# ArduinoUnoSCHEMATIC.net
KiCad netlist of a schematic drawn in Altium Designer
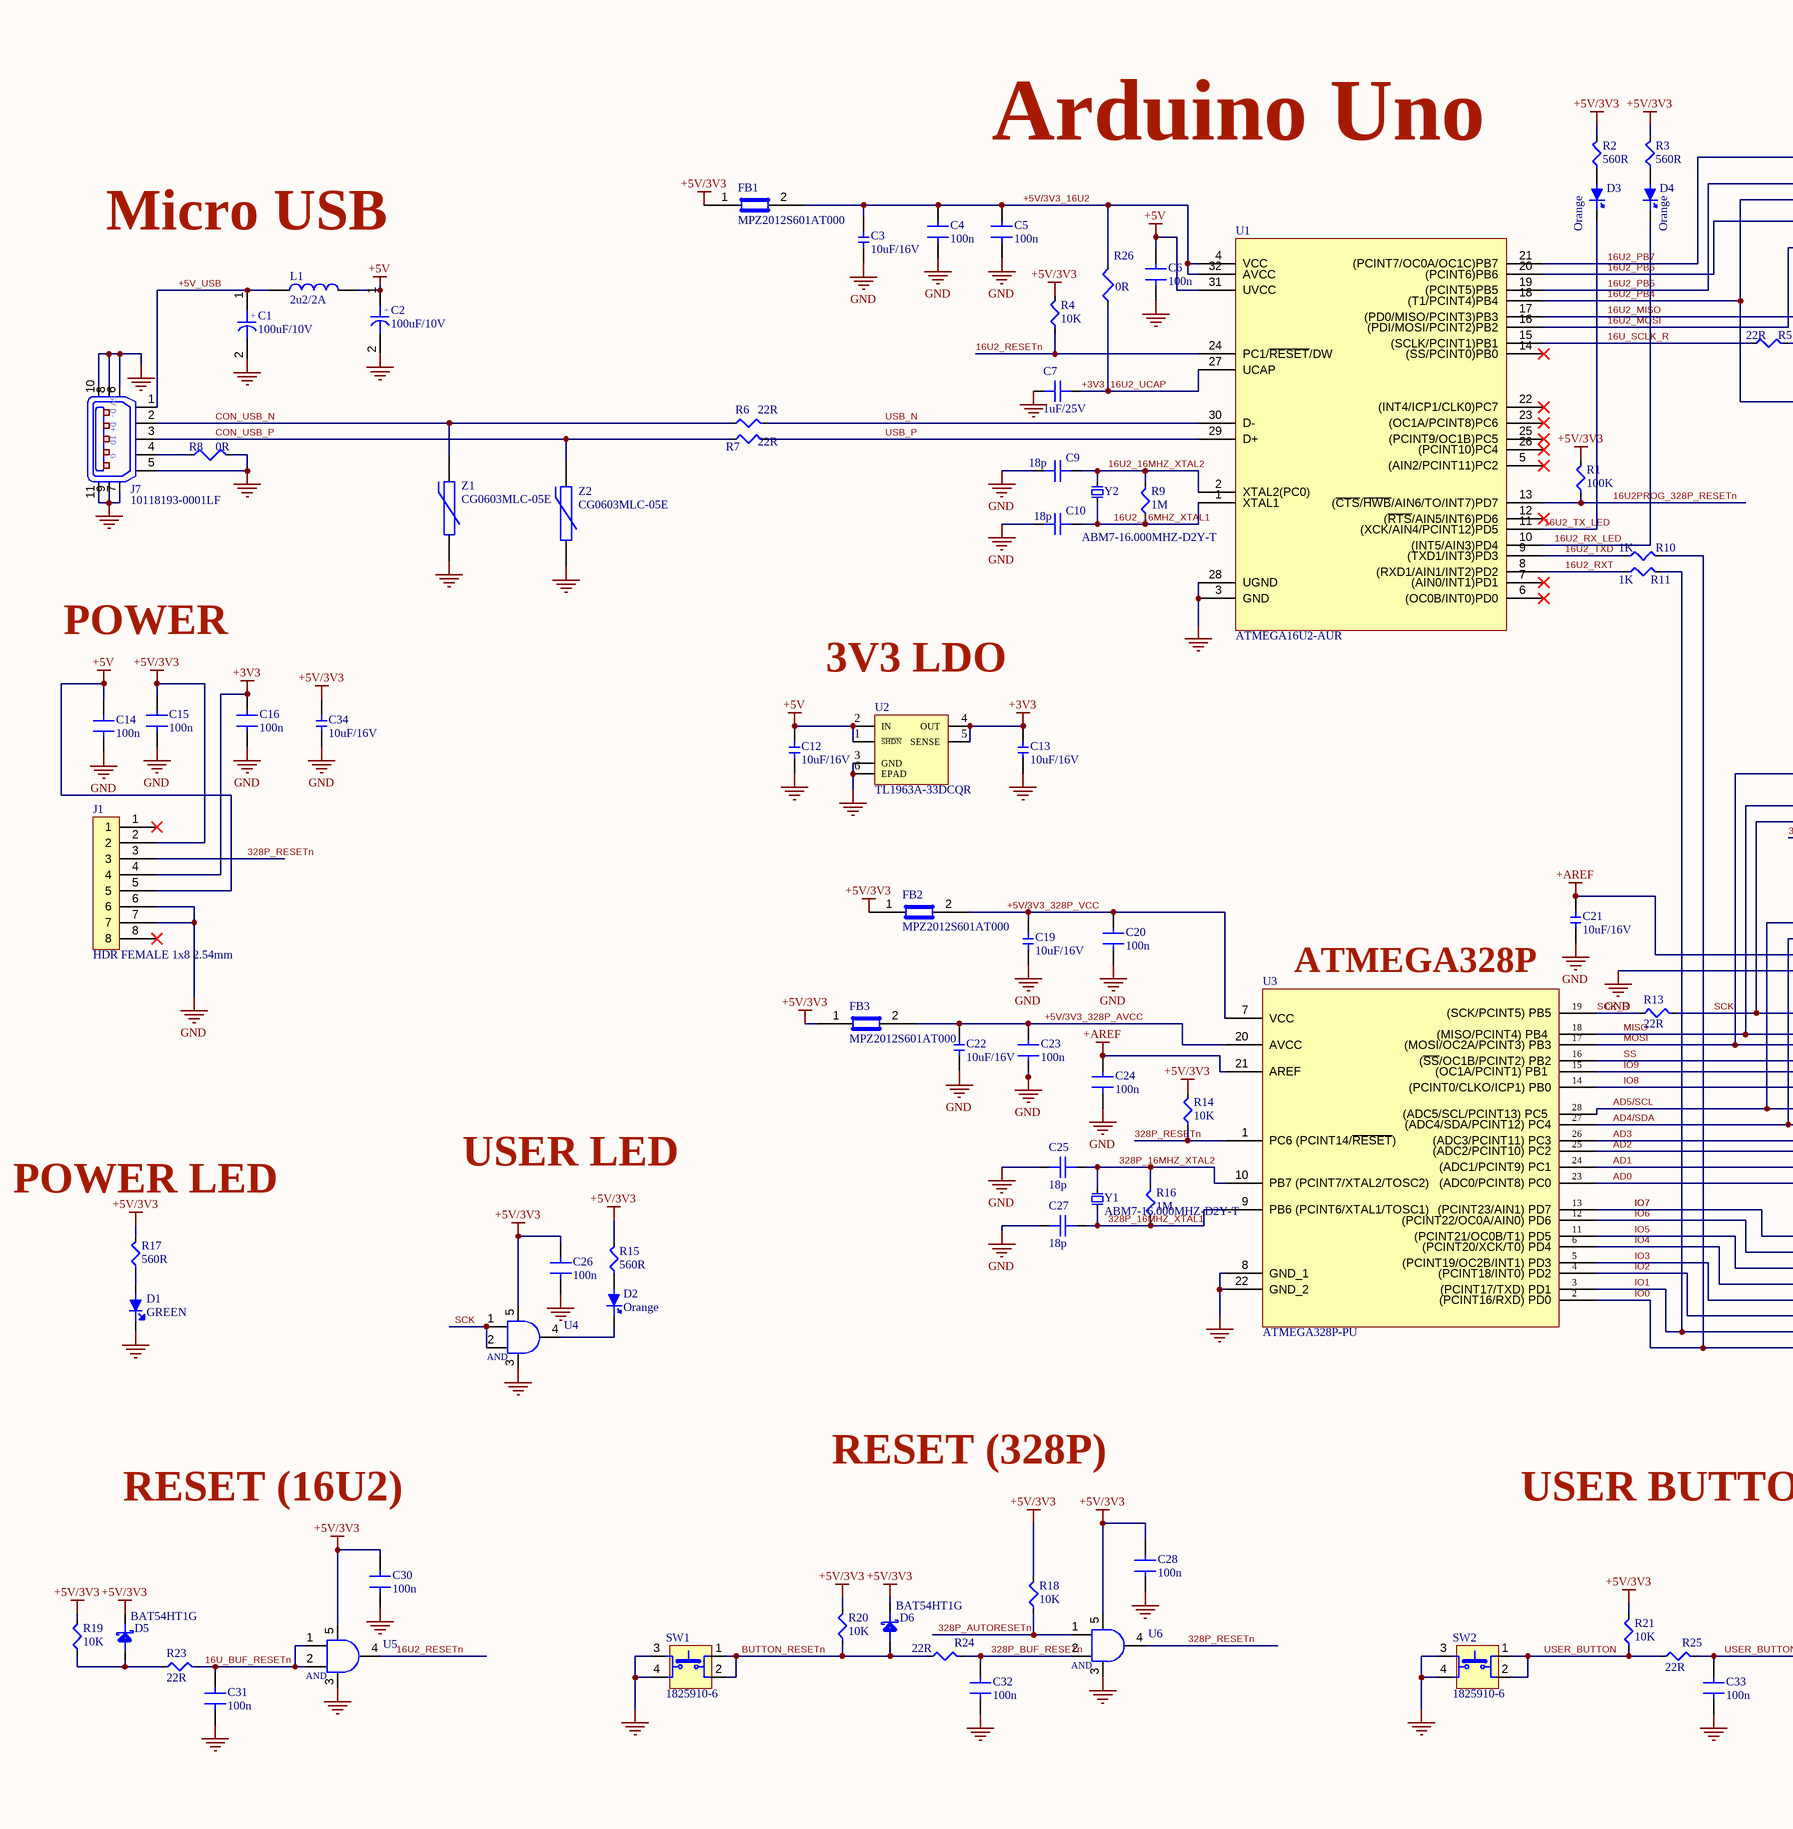
[diagram p0: ArduinoUnoSCHEMATIC.SchDoc, left]
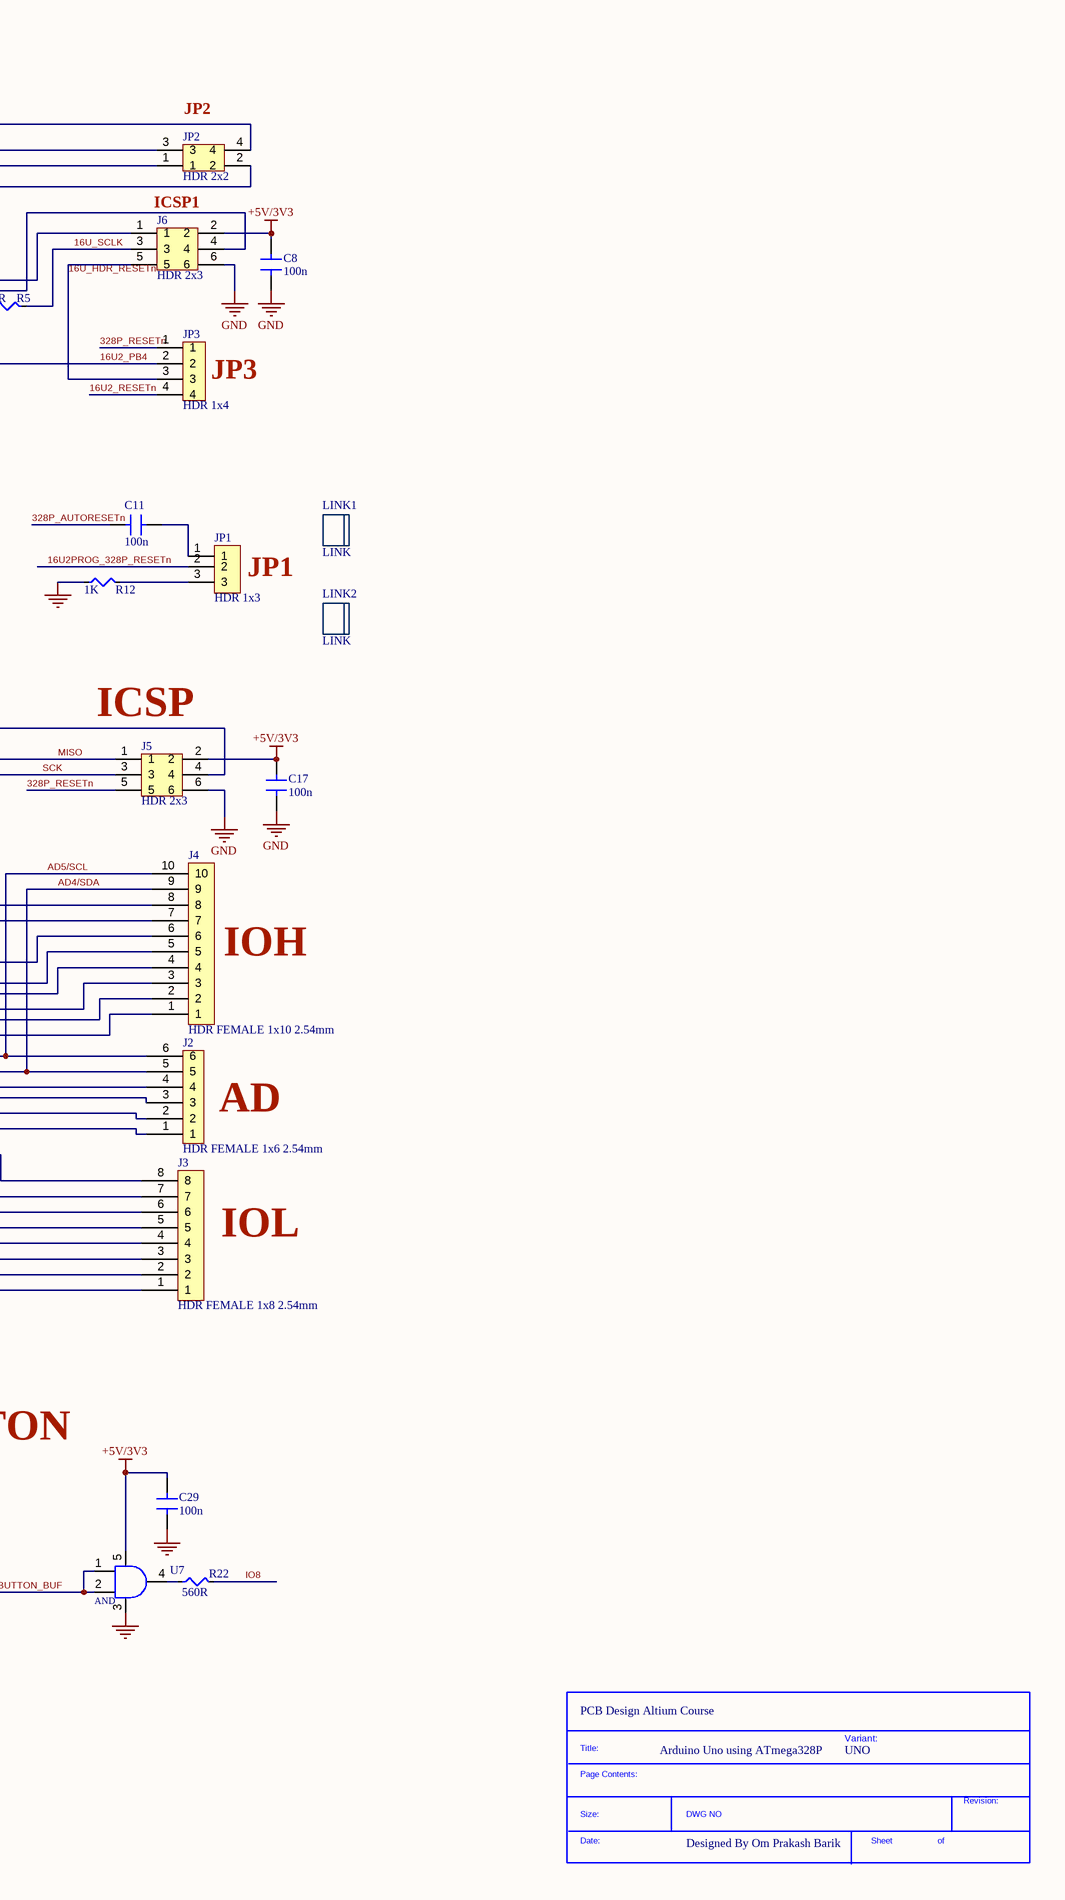
[diagram p1: ArduinoUnoSCHEMATIC.SchDoc, right]

(export (version "E")
  (design (tool "Eeschema 10.0.6"))
  (components
    (comp (ref "1") (value "~") (description "1") (libsource (lib "*") (part "SDTitleBlock")))
    (comp (ref "C1")
      (value "100uF/10V")
      (footprint "C_ALMN_CSIZE")
      (description "Cap Aluminum 100uF 10V 20% (5 X 5.4mm) SMD 50mA 1000 hr 85°C T/R")
      (fields
        (field (name "MANUFACTURER") "Panasonic")
        (field (name "MANUFACTURER PART NUMBER") "EEE-1AA101WR")
      )
      (libsource (lib "EmbedUno_V1I1") (part "100uF/10V"))
    )
    (comp (ref "C2")
      (value "100uF/10V")
      (footprint "C_ALMN_CSIZE")
      (description "Cap Aluminum 100uF 10V 20% (5 X 5.4mm) SMD 50mA 1000 hr 85°C T/R")
      (fields
        (field (name "MANUFACTURER") "Panasonic")
        (field (name "MANUFACTURER PART NUMBER") "EEE-1AA101WR")
      )
      (libsource (lib "EmbedUno_V1I1") (part "100uF/10V"))
    )
    (comp (ref "C3")
      (value "10uF/16V")
      (footprint "C0805")
      (fields
        (field (name "MANUFACTURER") "TDK")
        (field (name "MANUFACTURER PART NUMBER") "C2012X5R1C106M085AC")
        (field (name "TOLERANCE") "20%")
      )
      (libsource (lib "EmbedUno_V1I1") (part "10uF/16V"))
    )
    (comp (ref "C4")
      (value "100n")
      (footprint "C0805")
      (description "CAP CER 0.1UF 50V X7R 0805")
      (fields
        (field (name "MANUFACTURER") "TDK")
        (field (name "MANUFACTURER PART NUMBER") "C2012X7R1H104M085AA")
      )
      (libsource (lib "EmbedUno_V1I1") (part "Cap 100n"))
    )
    (comp (ref "C5")
      (value "100n")
      (footprint "C0805")
      (description "CAP CER 0.1UF 50V X7R 0805")
      (fields
        (field (name "MANUFACTURER") "TDK")
        (field (name "MANUFACTURER PART NUMBER") "C2012X7R1H104M085AA")
      )
      (libsource (lib "EmbedUno_V1I1") (part "Cap 100n"))
    )
    (comp (ref "C6")
      (value "100n")
      (footprint "C0805")
      (description "CAP CER 0.1UF 50V X7R 0805")
      (fields
        (field (name "MANUFACTURER") "TDK")
        (field (name "MANUFACTURER PART NUMBER") "C2012X7R1H104M085AA")
      )
      (libsource (lib "EmbedUno_V1I1") (part "Cap 100n"))
    )
    (comp (ref "C7")
      (value "1uF/25V")
      (footprint "C0805")
      (description "CAP CER 1UF 25V JB 0805")
      (fields
        (field (name "MANUFACTURER") "TDK")
        (field (name "MANUFACTURER PART NUMBER") "C2012JB1E105K125AA")
      )
      (libsource (lib "EmbedUno_V1I1") (part "1uF"))
    )
    (comp (ref "C8")
      (value "100n")
      (footprint "C0805")
      (description "CAP CER 0.1UF 50V X7R 0805")
      (fields
        (field (name "MANUFACTURER") "TDK")
        (field (name "MANUFACTURER PART NUMBER") "C2012X7R1H104M085AA")
      )
      (libsource (lib "EmbedUno_V1I1") (part "Cap 100n"))
    )
    (comp (ref "C9")
      (value "18p")
      (footprint "C0805")
      (description "CAP CER 18PF 50V C0G/NP0 0805")
      (fields
        (field (name "MANUFACTURER") "KEMET")
        (field (name "MANUFACTURER PART NUMBER") "C0805C180J5GACTU")
      )
      (libsource (lib "EmbedUno_V1I1") (part "C0805C180J5GACTU"))
    )
    (comp (ref "C10")
      (value "18p")
      (footprint "C0805")
      (description "CAP CER 18PF 50V C0G/NP0 0805")
      (fields
        (field (name "MANUFACTURER") "KEMET")
        (field (name "MANUFACTURER PART NUMBER") "C0805C180J5GACTU")
      )
      (libsource (lib "EmbedUno_V1I1") (part "C0805C180J5GACTU"))
    )
    (comp (ref "C11")
      (value "100n")
      (footprint "C0805")
      (description "CAP CER 0.1UF 50V X7R 0805")
      (fields
        (field (name "MANUFACTURER") "TDK")
        (field (name "MANUFACTURER PART NUMBER") "C2012X7R1H104M085AA")
      )
      (libsource (lib "EmbedUno_V1I1") (part "Cap 100n"))
    )
    (comp (ref "C12")
      (value "10uF/16V")
      (footprint "C0805")
      (fields
        (field (name "MANUFACTURER") "TDK")
        (field (name "MANUFACTURER PART NUMBER") "C2012X5R1C106M085AC")
        (field (name "TOLERANCE") "20%")
      )
      (libsource (lib "EmbedUno_V1I1") (part "10uF/16V"))
    )
    (comp (ref "C13")
      (value "10uF/16V")
      (footprint "C0805")
      (fields
        (field (name "MANUFACTURER") "TDK")
        (field (name "MANUFACTURER PART NUMBER") "C2012X5R1C106M085AC")
        (field (name "TOLERANCE") "20%")
      )
      (libsource (lib "EmbedUno_V1I1") (part "10uF/16V"))
    )
    (comp (ref "C14")
      (value "100n")
      (footprint "C0805")
      (description "CAP CER 0.1UF 50V X7R 0805")
      (fields
        (field (name "MANUFACTURER") "TDK")
        (field (name "MANUFACTURER PART NUMBER") "C2012X7R1H104M085AA")
      )
      (libsource (lib "EmbedUno_V1I1") (part "Cap 100n"))
    )
    (comp (ref "C15")
      (value "100n")
      (footprint "C0805")
      (description "CAP CER 0.1UF 50V X7R 0805")
      (fields
        (field (name "MANUFACTURER") "TDK")
        (field (name "MANUFACTURER PART NUMBER") "C2012X7R1H104M085AA")
      )
      (libsource (lib "EmbedUno_V1I1") (part "Cap 100n"))
    )
    (comp (ref "C16")
      (value "100n")
      (footprint "C0805")
      (description "CAP CER 0.1UF 50V X7R 0805")
      (fields
        (field (name "MANUFACTURER") "TDK")
        (field (name "MANUFACTURER PART NUMBER") "C2012X7R1H104M085AA")
      )
      (libsource (lib "EmbedUno_V1I1") (part "Cap 100n"))
    )
    (comp (ref "C17")
      (value "100n")
      (footprint "C0805")
      (description "CAP CER 0.1UF 50V X7R 0805")
      (fields
        (field (name "MANUFACTURER") "TDK")
        (field (name "MANUFACTURER PART NUMBER") "C2012X7R1H104M085AA")
      )
      (libsource (lib "EmbedUno_V1I1") (part "Cap 100n"))
    )
    (comp (ref "C19")
      (value "10uF/16V")
      (footprint "C0805")
      (fields
        (field (name "MANUFACTURER") "TDK")
        (field (name "MANUFACTURER PART NUMBER") "C2012X5R1C106M085AC")
        (field (name "TOLERANCE") "20%")
      )
      (libsource (lib "EmbedUno_V1I1") (part "10uF/16V"))
    )
    (comp (ref "C20")
      (value "100n")
      (footprint "C0805")
      (description "CAP CER 0.1UF 50V X7R 0805")
      (fields
        (field (name "MANUFACTURER") "TDK")
        (field (name "MANUFACTURER PART NUMBER") "C2012X7R1H104M085AA")
      )
      (libsource (lib "EmbedUno_V1I1") (part "Cap 100n"))
    )
    (comp (ref "C21")
      (value "10uF/16V")
      (footprint "C0805")
      (fields
        (field (name "MANUFACTURER") "TDK")
        (field (name "MANUFACTURER PART NUMBER") "C2012X5R1C106M085AC")
        (field (name "TOLERANCE") "20%")
      )
      (libsource (lib "EmbedUno_V1I1") (part "10uF/16V"))
    )
    (comp (ref "C22")
      (value "10uF/16V")
      (footprint "C0805")
      (fields
        (field (name "MANUFACTURER") "TDK")
        (field (name "MANUFACTURER PART NUMBER") "C2012X5R1C106M085AC")
        (field (name "TOLERANCE") "20%")
      )
      (libsource (lib "EmbedUno_V1I1") (part "10uF/16V"))
    )
    (comp (ref "C23")
      (value "100n")
      (footprint "C0805")
      (description "CAP CER 0.1UF 50V X7R 0805")
      (fields
        (field (name "MANUFACTURER") "TDK")
        (field (name "MANUFACTURER PART NUMBER") "C2012X7R1H104M085AA")
      )
      (libsource (lib "EmbedUno_V1I1") (part "Cap 100n"))
    )
    (comp (ref "C24")
      (value "100n")
      (footprint "C0805")
      (description "CAP CER 0.1UF 50V X7R 0805")
      (fields
        (field (name "MANUFACTURER") "TDK")
        (field (name "MANUFACTURER PART NUMBER") "C2012X7R1H104M085AA")
      )
      (libsource (lib "EmbedUno_V1I1") (part "Cap 100n"))
    )
    (comp (ref "C25")
      (value "18p")
      (footprint "C0805")
      (description "CAP CER 18PF 50V C0G/NP0 0805")
      (fields
        (field (name "MANUFACTURER") "KEMET")
        (field (name "MANUFACTURER PART NUMBER") "C0805C180J5GACTU")
      )
      (libsource (lib "EmbedUno_V1I1") (part "C0805C180J5GACTU"))
    )
    (comp (ref "C26")
      (value "100n")
      (footprint "C0805")
      (description "CAP CER 0.1UF 50V X7R 0805")
      (fields
        (field (name "MANUFACTURER") "TDK")
        (field (name "MANUFACTURER PART NUMBER") "C2012X7R1H104M085AA")
      )
      (libsource (lib "EmbedUno_V1I1") (part "Cap 100n"))
    )
    (comp (ref "C27")
      (value "18p")
      (footprint "C0805")
      (description "CAP CER 18PF 50V C0G/NP0 0805")
      (fields
        (field (name "MANUFACTURER") "KEMET")
        (field (name "MANUFACTURER PART NUMBER") "C0805C180J5GACTU")
      )
      (libsource (lib "EmbedUno_V1I1") (part "C0805C180J5GACTU"))
    )
    (comp (ref "C28")
      (value "100n")
      (footprint "C0805")
      (description "CAP CER 0.1UF 50V X7R 0805")
      (fields
        (field (name "MANUFACTURER") "TDK")
        (field (name "MANUFACTURER PART NUMBER") "C2012X7R1H104M085AA")
      )
      (libsource (lib "EmbedUno_V1I1") (part "Cap 100n"))
    )
    (comp (ref "C29")
      (value "100n")
      (footprint "C0805")
      (description "CAP CER 0.1UF 50V X7R 0805")
      (fields
        (field (name "MANUFACTURER") "TDK")
        (field (name "MANUFACTURER PART NUMBER") "C2012X7R1H104M085AA")
      )
      (libsource (lib "EmbedUno_V1I1") (part "Cap 100n"))
    )
    (comp (ref "C30")
      (value "100n")
      (footprint "C0805")
      (description "CAP CER 0.1UF 50V X7R 0805")
      (fields
        (field (name "MANUFACTURER") "TDK")
        (field (name "MANUFACTURER PART NUMBER") "C2012X7R1H104M085AA")
      )
      (libsource (lib "EmbedUno_V1I1") (part "Cap 100n"))
    )
    (comp (ref "C31")
      (value "100n")
      (footprint "C0805")
      (description "CAP CER 0.1UF 50V X7R 0805")
      (fields
        (field (name "MANUFACTURER") "TDK")
        (field (name "MANUFACTURER PART NUMBER") "C2012X7R1H104M085AA")
      )
      (libsource (lib "EmbedUno_V1I1") (part "Cap 100n"))
    )
    (comp (ref "C32")
      (value "100n")
      (footprint "C0805")
      (description "CAP CER 0.1UF 50V X7R 0805")
      (fields
        (field (name "MANUFACTURER") "TDK")
        (field (name "MANUFACTURER PART NUMBER") "C2012X7R1H104M085AA")
      )
      (libsource (lib "EmbedUno_V1I1") (part "Cap 100n"))
    )
    (comp (ref "C33")
      (value "100n")
      (footprint "C0805")
      (description "CAP CER 0.1UF 50V X7R 0805")
      (fields
        (field (name "MANUFACTURER") "TDK")
        (field (name "MANUFACTURER PART NUMBER") "C2012X7R1H104M085AA")
      )
      (libsource (lib "EmbedUno_V1I1") (part "Cap 100n"))
    )
    (comp (ref "C34")
      (value "10uF/16V")
      (footprint "C0805")
      (fields
        (field (name "MANUFACTURER") "TDK")
        (field (name "MANUFACTURER PART NUMBER") "C2012X5R1C106M085AC")
        (field (name "TOLERANCE") "20%")
      )
      (libsource (lib "EmbedUno_V1I1") (part "10uF/16V"))
    )
    (comp (ref "D1")
      (value "GREEN")
      (footprint "LED_0603")
      (description "LED Uni-Color Green 572nm 2-Pin Chip 0603(1608Metric) T/R")
      (fields
        (field (name "MANUFACTURER") "Osram Opto")
        (field (name "MANUFACTURER PART NUMBER") "LGL29K-G2J1-24-Z")
      )
      (libsource (lib "EmbedUno_V1I1") (part "GREEN"))
    )
    (comp (ref "D2")
      (value "Orange")
      (footprint "LED_0603")
      (description "OSRAM - LO L29K-H2K1-24-Z - SMARTLED 0603 ORANGE")
      (fields
        (field (name "MANUFACTURER") "Osram Opto")
        (field (name "MANUFACTURER PART NUMBER") "LOL29K-H2K1-24-Z")
      )
      (libsource (lib "EmbedUno_V1I1") (part "Orange LED"))
    )
    (comp (ref "D3")
      (value "Orange")
      (footprint "LED_0603")
      (description "OSRAM - LO L29K-H2K1-24-Z - SMARTLED 0603 ORANGE")
      (fields
        (field (name "MANUFACTURER") "Osram Opto")
        (field (name "MANUFACTURER PART NUMBER") "LOL29K-H2K1-24-Z")
      )
      (libsource (lib "EmbedUno_V1I1") (part "Orange LED"))
    )
    (comp (ref "D4")
      (value "Orange")
      (footprint "LED_0603")
      (description "OSRAM - LO L29K-H2K1-24-Z - SMARTLED 0603 ORANGE")
      (fields
        (field (name "MANUFACTURER") "Osram Opto")
        (field (name "MANUFACTURER PART NUMBER") "LOL29K-H2K1-24-Z")
      )
      (libsource (lib "EmbedUno_V1I1") (part "Orange LED"))
    )
    (comp (ref "D5")
      (value "BAT54HT1G")
      (footprint "SOD323")
      (description "Small Signal Schottky Diode, Single, 30 V, 200 mA, 800 mV, 600 mA, 150 C ;RoHS Compliant: Yes")
      (fields (field (name "MANUFACTURER") "ON Semiconductor / Fairchild"))
      (libsource (lib "EmbedUno_V1I1") (part "BAT54HT1G"))
    )
    (comp (ref "D6")
      (value "BAT54HT1G")
      (footprint "SOD323")
      (description "Small Signal Schottky Diode, Single, 30 V, 200 mA, 800 mV, 600 mA, 150 C ;RoHS Compliant: Yes")
      (fields (field (name "MANUFACTURER") "ON Semiconductor / Fairchild"))
      (libsource (lib "EmbedUno_V1I1") (part "BAT54HT1G"))
    )
    (comp (ref "FB1")
      (value "MPZ2012S601AT000")
      (footprint "C0805")
      (description "FERRITE BEAD 600 OHM 0805 1LN")
      (fields (field (name "MANUFACTURER") "TDK"))
      (libsource (lib "EmbedUno_V1I1") (part "MPZ2012S601AT000"))
    )
    (comp (ref "FB2")
      (value "MPZ2012S601AT000")
      (footprint "C0805")
      (description "FERRITE BEAD 600 OHM 0805 1LN")
      (fields (field (name "MANUFACTURER") "TDK"))
      (libsource (lib "EmbedUno_V1I1") (part "MPZ2012S601AT000"))
    )
    (comp (ref "FB3")
      (value "MPZ2012S601AT000")
      (footprint "C0805")
      (description "FERRITE BEAD 600 OHM 0805 1LN")
      (fields (field (name "MANUFACTURER") "TDK"))
      (libsource (lib "EmbedUno_V1I1") (part "MPZ2012S601AT000"))
    )
    (comp (ref "J1")
      (value "HDR FEMALE 1x8 2.54mm")
      (footprint "HDR_Female_1x8_2.54mm")
      (description "2.54mm (0.1\") Pitch SIL Vertical PC Tail Socket Assembly, selective gold + tin, 8 contacts")
      (fields (field (name "MANUFACTURER") "Harwin") (field (name "MANUFACTURER PART NUMBER") "M20-7820842"))
      (libsource (lib "EmbedUno_V1I1") (part "M20-7820842"))
    )
    (comp (ref "J2")
      (value "HDR FEMALE 1x6 2.54mm")
      (footprint "HDR_Female_1x6_2.54mm")
      (fields (field (name "MANUFACTURER") "Harwin") (field (name "MANUFACTURER PART NUMBER") "M20-7820646"))
      (libsource (lib "EmbedUno_V1I1") (part "M20-7820646"))
    )
    (comp (ref "J3")
      (value "HDR FEMALE 1x8 2.54mm")
      (footprint "HDR_Female_1x8_2.54mm")
      (description "2.54mm (0.1\") Pitch SIL Vertical PC Tail Socket Assembly, selective gold + tin, 8 contacts")
      (fields (field (name "MANUFACTURER") "Harwin") (field (name "MANUFACTURER PART NUMBER") "M20-7820842"))
      (libsource (lib "") (part "M20-7820842_1"))
    )
    (comp (ref "J4")
      (value "HDR FEMALE 1x10 2.54mm")
      (footprint "HDR_Female_1x10_2.54mm")
      (fields (field (name "MANUFACTURER") "Harwin") (field (name "MANUFACTURER PART NUMBER") "M20-7821046"))
      (libsource (lib "EmbedUno_V1I1") (part "M20-7821046"))
    )
    (comp (ref "J5")
      (value "HDR 2x3")
      (footprint "HDR 2x3")
      (description "CONN HEADER 6POS .100 STR 30AU")
      (fields
        (field (name "MANUFACTURER") "Amphenol FCI")
        (field (name "MANUFACTURER PART NUMBER") "67997-106HLF")
      )
      (libsource (lib "EmbedUno_V1I1") (part "HDR 2x3"))
    )
    (comp (ref "J6")
      (value "HDR 2x3")
      (footprint "HDR 2x3")
      (description "CONN HEADER 6POS .100 STR 30AU")
      (fields
        (field (name "MANUFACTURER") "Amphenol FCI")
        (field (name "MANUFACTURER PART NUMBER") "67997-106HLF")
      )
      (libsource (lib "EmbedUno_V1I1") (part "HDR 2x3"))
    )
    (comp (ref "J7")
      (value "10118193-0001LF")
      (footprint "10118193-0001LF")
      (description "CONN USB MICRO B RECPT SMT R/A")
      (fields (field (name "MANUFACTURER") "Amphenol FCI"))
      (libsource (lib "EmbedUno_V1I1") (part "USB_CON"))
    )
    (comp (ref "JP1")
      (value "HDR 1x3")
      (footprint "HDR_Male_1x3_2.54mm")
      (fields
        (field (name "MANUFACTURER") "Amphenol FCI")
        (field (name "MANUFACTURER PART NUMBER") "68000-103HLF")
      )
      (libsource (lib "EmbedUno_V1I1") (part "68000-103HLF"))
    )
    (comp (ref "JP2")
      (value "HDR 2x2")
      (footprint "HDR 2x2_2.54mm")
      (description "CONN HEADER VERT 4POS 2.54MM")
      (fields
        (field (name "MANUFACTURER") "Amphenol FCI")
        (field (name "MANUFACTURER PART NUMBER") "68602-204HLF")
      )
      (libsource (lib "EmbedUno_V1I1") (part "HDR_2x2"))
    )
    (comp (ref "JP3")
      (value "HDR 1x4")
      (footprint "HDR_1x4_2.54mm")
      (description "CONN HEADER VERT 4POS 2.54MM")
      (fields
        (field (name "MANUFACTURER") "Amphenol FCI")
        (field (name "MANUFACTURER PART NUMBER") "68001-204HLF")
      )
      (libsource (lib "EmbedUno_V1I1") (part "HDR 1x4"))
    )
    (comp (ref "L1")
      (value "2u2/2A")
      (footprint "CL210_IND")
      (description "FIXED IND 2.2UH 2A 80 MOHM SMD")
      (fields
        (field (name "MANUFACTURER") "KEMET")
        (field (name "MANUFACTURER PART NUMBER") "L1210R2R2MDWIT")
      )
      (libsource (lib "EmbedUno_V1I1") (part "2u2/2A"))
    )
    (comp (ref "LINK1")
      (value "LINK")
      (description "CONN JUMPER SHORTING .100\" GOLD")
      (fields
        (field (name "MANUFACTURER") "Sullins")
        (field (name "MANUFACTURER PART NUMBER") "QPC02SXGN-RC")
      )
      (libsource (lib "EmbedUno_V1I1") (part "LINK"))
    )
    (comp (ref "LINK2")
      (value "LINK")
      (description "CONN JUMPER SHORTING .100\" GOLD")
      (fields
        (field (name "MANUFACTURER") "Sullins")
        (field (name "MANUFACTURER PART NUMBER") "QPC02SXGN-RC")
      )
      (libsource (lib "EmbedUno_V1I1") (part "LINK"))
    )
    (comp (ref "R1")
      (value "100K")
      (footprint "R0805")
      (description "RES SMD 100K OHM 0.1% 1/8W 0805")
      (fields
        (field (name "MANUFACTURER") "Yageo")
        (field (name "MANUFACTURER PART NUMBER") "RT0805BRD07100KL")
      )
      (libsource (lib "EmbedUno_V1I1") (part "100K"))
    )
    (comp (ref "R2")
      (value "560R")
      (footprint "R0805")
      (description "RES SMD 560 OHM 1% 1/8W 0805")
      (fields
        (field (name "MANUFACTURER") "Yageo")
        (field (name "MANUFACTURER PART NUMBER") "RT0805FRE07560RL")
      )
      (libsource (lib "EmbedUno_V1I1") (part "560R"))
    )
    (comp (ref "R3")
      (value "560R")
      (footprint "R0805")
      (description "RES SMD 560 OHM 1% 1/8W 0805")
      (fields
        (field (name "MANUFACTURER") "Yageo")
        (field (name "MANUFACTURER PART NUMBER") "RT0805FRE07560RL")
      )
      (libsource (lib "EmbedUno_V1I1") (part "560R"))
    )
    (comp (ref "R4")
      (value "10K")
      (footprint "R0805")
      (description "Res SMD 10K Ohm 1% 1/8W 0805")
      (fields
        (field (name "MANUFACTURER") "Yageo")
        (field (name "MANUFACTURER PART NUMBER") "AF0805FR-0710KL")
      )
      (libsource (lib "EmbedUno_V1I1") (part "AF0805FR-0710KL"))
    )
    (comp (ref "R5")
      (value "22R")
      (footprint "R0805")
      (description "RES SMD 22 OHM 1% 1/8W 0805")
      (fields
        (field (name "MANUFACTURER") "Yageo")
        (field (name "MANUFACTURER PART NUMBER") "RC0805FR-0722RL")
      )
      (libsource (lib "EmbedUno_V1I1") (part "RC0805FR-0722RL"))
    )
    (comp (ref "R6")
      (value "22R")
      (footprint "R0805")
      (description "RES SMD 22 OHM 1% 1/8W 0805")
      (fields
        (field (name "MANUFACTURER") "Yageo")
        (field (name "MANUFACTURER PART NUMBER") "RC0805FR-0722RL")
      )
      (libsource (lib "EmbedUno_V1I1") (part "RC0805FR-0722RL"))
    )
    (comp (ref "R7")
      (value "22R")
      (footprint "R0805")
      (description "RES SMD 22 OHM 1% 1/8W 0805")
      (fields
        (field (name "MANUFACTURER") "Yageo")
        (field (name "MANUFACTURER PART NUMBER") "RC0805FR-0722RL")
      )
      (libsource (lib "EmbedUno_V1I1") (part "RC0805FR-0722RL"))
    )
    (comp (ref "R8")
      (value "0R")
      (footprint "R0805")
      (description "Resistor Thick Film Jumper 5% 0805 2-Pin Paper T/R")
      (fields
        (field (name "MANUFACTURER") "Yageo")
        (field (name "MANUFACTURER PART NUMBER") "RC0805JR-7W0RL")
      )
      (libsource (lib "EmbedUno_V1I1") (part "0R"))
    )
    (comp (ref "R9")
      (value "1M")
      (footprint "R0805")
      (description "RES SMD 1M OHM 1% 1/8W 0805")
      (fields
        (field (name "MANUFACTURER") "Yageo")
        (field (name "MANUFACTURER PART NUMBER") "RC0805FR-071ML")
      )
      (libsource (lib "EmbedUno_V1I1") (part "RC0805FR-071ML"))
    )
    (comp (ref "R10")
      (value "1K")
      (footprint "R0805")
      (description "RES SMD 1K OHM 1% 1/8W 0805")
      (fields
        (field (name "MANUFACTURER") "Yageo")
        (field (name "MANUFACTURER PART NUMBER") "RT0805FRE071KL")
      )
      (libsource (lib "EmbedUno_V1I1") (part "RT0805FRE071KL"))
    )
    (comp (ref "R11")
      (value "1K")
      (footprint "R0805")
      (description "RES SMD 1K OHM 1% 1/8W 0805")
      (fields
        (field (name "MANUFACTURER") "Yageo")
        (field (name "MANUFACTURER PART NUMBER") "RT0805FRE071KL")
      )
      (libsource (lib "EmbedUno_V1I1") (part "RT0805FRE071KL"))
    )
    (comp (ref "R12")
      (value "1K")
      (footprint "R0805")
      (description "RES SMD 1K OHM 1% 1/8W 0805")
      (fields
        (field (name "MANUFACTURER") "Yageo")
        (field (name "MANUFACTURER PART NUMBER") "RT0805FRE071KL")
      )
      (libsource (lib "EmbedUno_V1I1") (part "RT0805FRE071KL"))
    )
    (comp (ref "R13")
      (value "22R")
      (footprint "R0805")
      (description "RES SMD 22 OHM 1% 1/8W 0805")
      (fields
        (field (name "MANUFACTURER") "Yageo")
        (field (name "MANUFACTURER PART NUMBER") "RC0805FR-0722RL")
      )
      (libsource (lib "EmbedUno_V1I1") (part "RC0805FR-0722RL"))
    )
    (comp (ref "R14")
      (value "10K")
      (footprint "R0805")
      (description "Res SMD 10K Ohm 1% 1/8W 0805")
      (fields
        (field (name "MANUFACTURER") "Yageo")
        (field (name "MANUFACTURER PART NUMBER") "AF0805FR-0710KL")
      )
      (libsource (lib "EmbedUno_V1I1") (part "AF0805FR-0710KL"))
    )
    (comp (ref "R15")
      (value "560R")
      (footprint "R0805")
      (description "RES SMD 560 OHM 1% 1/8W 0805")
      (fields
        (field (name "MANUFACTURER") "Yageo")
        (field (name "MANUFACTURER PART NUMBER") "RT0805FRE07560RL")
      )
      (libsource (lib "EmbedUno_V1I1") (part "560R"))
    )
    (comp (ref "R16")
      (value "1M")
      (footprint "R0805")
      (description "RES SMD 1M OHM 1% 1/8W 0805")
      (fields
        (field (name "MANUFACTURER") "Yageo")
        (field (name "MANUFACTURER PART NUMBER") "RC0805FR-071ML")
      )
      (libsource (lib "EmbedUno_V1I1") (part "RC0805FR-071ML"))
    )
    (comp (ref "R17")
      (value "560R")
      (footprint "R0805")
      (description "RES SMD 560 OHM 1% 1/8W 0805")
      (fields
        (field (name "MANUFACTURER") "Yageo")
        (field (name "MANUFACTURER PART NUMBER") "RT0805FRE07560RL")
      )
      (libsource (lib "EmbedUno_V1I1") (part "560R"))
    )
    (comp (ref "R18")
      (value "10K")
      (footprint "R0805")
      (description "Res SMD 10K Ohm 1% 1/8W 0805")
      (fields
        (field (name "MANUFACTURER") "Yageo")
        (field (name "MANUFACTURER PART NUMBER") "AF0805FR-0710KL")
      )
      (libsource (lib "EmbedUno_V1I1") (part "AF0805FR-0710KL"))
    )
    (comp (ref "R19")
      (value "10K")
      (footprint "R0805")
      (description "Res SMD 10K Ohm 1% 1/8W 0805")
      (fields
        (field (name "MANUFACTURER") "Yageo")
        (field (name "MANUFACTURER PART NUMBER") "AF0805FR-0710KL")
      )
      (libsource (lib "EmbedUno_V1I1") (part "AF0805FR-0710KL"))
    )
    (comp (ref "R20")
      (value "10K")
      (footprint "R0805")
      (description "Res SMD 10K Ohm 1% 1/8W 0805")
      (fields
        (field (name "MANUFACTURER") "Yageo")
        (field (name "MANUFACTURER PART NUMBER") "AF0805FR-0710KL")
      )
      (libsource (lib "EmbedUno_V1I1") (part "AF0805FR-0710KL"))
    )
    (comp (ref "R21")
      (value "10K")
      (footprint "R0805")
      (description "Res SMD 10K Ohm 1% 1/8W 0805")
      (fields
        (field (name "MANUFACTURER") "Yageo")
        (field (name "MANUFACTURER PART NUMBER") "AF0805FR-0710KL")
      )
      (libsource (lib "EmbedUno_V1I1") (part "AF0805FR-0710KL"))
    )
    (comp (ref "R22")
      (value "560R")
      (footprint "R0805")
      (description "RES SMD 560 OHM 1% 1/8W 0805")
      (fields
        (field (name "MANUFACTURER") "Yageo")
        (field (name "MANUFACTURER PART NUMBER") "RT0805FRE07560RL")
      )
      (libsource (lib "EmbedUno_V1I1") (part "560R"))
    )
    (comp (ref "R23")
      (value "22R")
      (footprint "R0805")
      (description "RES SMD 22 OHM 1% 1/8W 0805")
      (fields
        (field (name "MANUFACTURER") "Yageo")
        (field (name "MANUFACTURER PART NUMBER") "RC0805FR-0722RL")
      )
      (libsource (lib "EmbedUno_V1I1") (part "RC0805FR-0722RL"))
    )
    (comp (ref "R24")
      (value "22R")
      (footprint "R0805")
      (description "RES SMD 22 OHM 1% 1/8W 0805")
      (fields
        (field (name "MANUFACTURER") "Yageo")
        (field (name "MANUFACTURER PART NUMBER") "RC0805FR-0722RL")
      )
      (libsource (lib "EmbedUno_V1I1") (part "RC0805FR-0722RL"))
    )
    (comp (ref "R25")
      (value "22R")
      (footprint "R0805")
      (description "RES SMD 22 OHM 1% 1/8W 0805")
      (fields
        (field (name "MANUFACTURER") "Yageo")
        (field (name "MANUFACTURER PART NUMBER") "RC0805FR-0722RL")
      )
      (libsource (lib "EmbedUno_V1I1") (part "RC0805FR-0722RL"))
    )
    (comp (ref "R26")
      (value "0R")
      (footprint "R0805")
      (description "Resistor Thick Film Jumper 5% 0805 2-Pin Paper T/R")
      (fields
        (field (name "MANUFACTURER") "Yageo")
        (field (name "MANUFACTURER PART NUMBER") "RC0805JR-7W0RL")
      )
      (libsource (lib "EmbedUno_V1I1") (part "0R"))
    )
    (comp (ref "SW1")
      (value "1825910-6")
      (footprint "1825910-6")
      (description "SWITCH TACTILE SPST-NO 0.05A 24V")
      (fields (field (name "MANUFACTURER") "TE Connectivity Alcoswitch"))
      (libsource (lib "EmbedUno_V1I1") (part "1825910-6"))
    )
    (comp (ref "SW2")
      (value "1825910-6")
      (footprint "1825910-6")
      (description "SWITCH TACTILE SPST-NO 0.05A 24V")
      (fields (field (name "MANUFACTURER") "TE Connectivity Alcoswitch"))
      (libsource (lib "EmbedUno_V1I1") (part "1825910-6"))
    )
    (comp (ref "U1")
      (value "ATMEGA16U2-AUR")
      (footprint "TQFP32")
      (description "IC MCU 8BIT 16KB FLASH 32TQFP")
      (fields (field (name "MANUFACTURER") "Microchip / Atmel"))
      (libsource (lib "EmbedUno_V1I1") (part "ATMEGA16U2-AUR"))
    )
    (comp (ref "U2")
      (value "TL1963A-33DCQR")
      (footprint "DCQ(R-PDSO-G6)")
      (description "IC REG LINEAR 3.3V 1.5A SOT223-6")
      (fields (field (name "MANUFACTURER") "Texas Instruments"))
      (libsource (lib "EmbedUno_V1I1") (part "TL1963A-33DCQR"))
    )
    (comp (ref "U3")
      (value "ATMEGA328P-PU")
      (footprint "28_DIP_7.62mm")
      (description "ATMEGA328P-PU; 8 bit Microcontroller AVR 20MHz 1; 32kb Flash; 2kb RAM; I2C SPI 2")
      (fields (field (name "MANUFACTURER") "Microchip / Atmel"))
      (libsource (lib "EmbedUno_V1I1") (part "ATMEGA328P-PU"))
    )
    (comp (ref "U4")
      (value "SN74AHC1G09DBVR")
      (footprint "DBV_SOP_23_5")
      (description "TEXAS INSTRUMENTS - SN74AHC1G09DBVR - AND Gate, 74AHC1G09, 2 Input, 2 V to 5.5 V, SOT-23-5")
      (fields (field (name "MANUFACTURER") "Texas Instruments"))
      (libsource (lib "EmbedUno_V1I1") (part "SN74AHC1G09DBVR"))
    )
    (comp (ref "U5")
      (value "SN74AHC1G09DBVR")
      (footprint "DBV_SOP_23_5")
      (description "TEXAS INSTRUMENTS - SN74AHC1G09DBVR - AND Gate, 74AHC1G09, 2 Input, 2 V to 5.5 V, SOT-23-5")
      (fields (field (name "MANUFACTURER") "Texas Instruments"))
      (libsource (lib "EmbedUno_V1I1") (part "SN74AHC1G09DBVR"))
    )
    (comp (ref "U6")
      (value "SN74AHC1G09DBVR")
      (footprint "DBV_SOP_23_5")
      (description "TEXAS INSTRUMENTS - SN74AHC1G09DBVR - AND Gate, 74AHC1G09, 2 Input, 2 V to 5.5 V, SOT-23-5")
      (fields (field (name "MANUFACTURER") "Texas Instruments"))
      (libsource (lib "EmbedUno_V1I1") (part "SN74AHC1G09DBVR"))
    )
    (comp (ref "U7")
      (value "SN74AHC1G09DBVR")
      (footprint "DBV_SOP_23_5")
      (description "TEXAS INSTRUMENTS - SN74AHC1G09DBVR - AND Gate, 74AHC1G09, 2 Input, 2 V to 5.5 V, SOT-23-5")
      (fields (field (name "MANUFACTURER") "Texas Instruments"))
      (libsource (lib "EmbedUno_V1I1") (part "SN74AHC1G09DBVR"))
    )
    (comp (ref "Y1")
      (value "ABM7-16.000MHZ-D2Y-T")
      (footprint "ABM7-v1_1_Big")
      (description "CRYSTAL 16.0000MHZ 18PF SMD")
      (fields (field (name "MANUFACTURER") "Abracon") (field (name "TOLERANCE") "20ppm"))
      (libsource (lib "EmbedUno_V1I1") (part "ABM7-16.000MHZ-D2Y-T"))
    )
    (comp (ref "Y2")
      (value "ABM7-16.000MHZ-D2Y-T")
      (footprint "ABM7-v1_1_Big")
      (description "CRYSTAL 16.0000MHZ 18PF SMD")
      (fields (field (name "MANUFACTURER") "Abracon") (field (name "TOLERANCE") "20ppm"))
      (libsource (lib "EmbedUno_V1I1") (part "ABM7-16.000MHZ-D2Y-T"))
    )
    (comp (ref "Z1")
      (value "CG0603MLC-05E")
      (footprint "R0603")
      (description "VARISTOR 0603")
      (fields (field (name "MANUFACTURER") "Bourns") (field (name "VOLTAGE") "5V"))
      (libsource (lib "EmbedUno_V1I1") (part "CG0603MLC-05E"))
    )
    (comp (ref "Z2")
      (value "CG0603MLC-05E")
      (footprint "R0603")
      (description "VARISTOR 0603")
      (fields (field (name "MANUFACTURER") "Bourns") (field (name "VOLTAGE") "5V"))
      (libsource (lib "EmbedUno_V1I1") (part "CG0603MLC-05E"))
    )
  )
  (nets
    (net (code "1") (name "+3V3") (class "Default")
      (node (ref "C13") (pin "2") (pinfunction "2_2") (pintype "passive"))
      (node (ref "C16") (pin "2") (pinfunction "2_2") (pintype "passive"))
      (node (ref "J1") (pin "4") (pinfunction "4_4") (pintype "passive"))
      (node (ref "U2") (pin "4") (pinfunction "OUT_4") (pintype "passive"))
      (node (ref "U2") (pin "5") (pinfunction "SENSE_5") (pintype "passive"))
    )
    (net (code "2") (name "+5V") (class "Default")
      (node (ref "C12") (pin "2") (pinfunction "2_2") (pintype "passive"))
      (node (ref "C14") (pin "2") (pinfunction "2_2") (pintype "passive"))
      (node (ref "C2") (pin "1") (pinfunction "1_1") (pintype "passive"))
      (node (ref "C6") (pin "2") (pinfunction "2_2") (pintype "passive"))
      (node (ref "J1") (pin "5") (pinfunction "5_5") (pintype "passive"))
      (node (ref "L1") (pin "2") (pinfunction "2_2") (pintype "passive"))
      (node (ref "U1") (pin "31") (pinfunction "UVCC_31") (pintype "passive"))
      (node (ref "U2") (pin "1") (pinfunction "~{SHDN}_1") (pintype "passive"))
      (node (ref "U2") (pin "2") (pinfunction "IN_2") (pintype "passive"))
    )
    (net (code "3") (name "+5V{slash}3V3") (class "Default")
      (node (ref "C15") (pin "2") (pinfunction "2_2") (pintype "passive"))
      (node (ref "C17") (pin "2") (pinfunction "2_2") (pintype "passive"))
      (node (ref "C26") (pin "2") (pinfunction "2_2") (pintype "passive"))
      (node (ref "C28") (pin "2") (pinfunction "2_2") (pintype "passive"))
      (node (ref "C29") (pin "2") (pinfunction "2_2") (pintype "passive"))
      (node (ref "C30") (pin "2") (pinfunction "2_2") (pintype "passive"))
      (node (ref "C34") (pin "2") (pinfunction "2_2") (pintype "passive"))
      (node (ref "C8") (pin "2") (pinfunction "2_2") (pintype "passive"))
      (node (ref "D5") (pin "1") (pinfunction "Cathode_1") (pintype "passive"))
      (node (ref "D6") (pin "1") (pinfunction "Cathode_1") (pintype "passive"))
      (node (ref "FB1") (pin "1") (pinfunction "1_1") (pintype "passive"))
      (node (ref "FB2") (pin "1") (pinfunction "1_1") (pintype "passive"))
      (node (ref "FB3") (pin "1") (pinfunction "1_1") (pintype "passive"))
      (node (ref "J1") (pin "2") (pinfunction "2_2") (pintype "passive"))
      (node (ref "J5") (pin "2") (pinfunction "2_2") (pintype "passive"))
      (node (ref "J6") (pin "2") (pinfunction "2_2") (pintype "passive"))
      (node (ref "R1") (pin "2") (pinfunction "2_2") (pintype "passive"))
      (node (ref "R14") (pin "2") (pinfunction "2_2") (pintype "passive"))
      (node (ref "R15") (pin "2") (pinfunction "2_2") (pintype "passive"))
      (node (ref "R17") (pin "2") (pinfunction "2_2") (pintype "passive"))
      (node (ref "R18") (pin "2") (pinfunction "2_2") (pintype "passive"))
      (node (ref "R19") (pin "2") (pinfunction "2_2") (pintype "passive"))
      (node (ref "R2") (pin "2") (pinfunction "2_2") (pintype "passive"))
      (node (ref "R20") (pin "2") (pinfunction "2_2") (pintype "passive"))
      (node (ref "R21") (pin "2") (pinfunction "2_2") (pintype "passive"))
      (node (ref "R3") (pin "2") (pinfunction "2_2") (pintype "passive"))
      (node (ref "R4") (pin "2") (pinfunction "2_2") (pintype "passive"))
      (node (ref "U4") (pin "5") (pinfunction "5_5") (pintype "passive"))
      (node (ref "U5") (pin "5") (pinfunction "5_5") (pintype "passive"))
      (node (ref "U6") (pin "5") (pinfunction "5_5") (pintype "passive"))
      (node (ref "U7") (pin "5") (pinfunction "5_5") (pintype "passive"))
    )
    (net (code "4") (name "+AREF") (class "Default")
      (node (ref "C21") (pin "2") (pinfunction "2_2") (pintype "passive"))
      (node (ref "C24") (pin "1") (pinfunction "1_1") (pintype "passive"))
      (node (ref "J4") (pin "8") (pinfunction "8_8") (pintype "passive"))
      (node (ref "U3") (pin "21") (pinfunction "AREF_21") (pintype "passive"))
    )
    (net (code "5") (name "/+3V3_16U2_UCAP") (class "Default")
      (node (ref "C7") (pin "2") (pinfunction "2_2") (pintype "passive"))
      (node (ref "R26") (pin "1") (pinfunction "1_1") (pintype "passive"))
      (node (ref "U1") (pin "27") (pinfunction "UCAP_27") (pintype "passive"))
    )
    (net (code "6") (name "/+5V_USB") (class "Default")
      (node (ref "C1") (pin "1") (pinfunction "1_1") (pintype "passive"))
      (node (ref "J7") (pin "1") (pinfunction "1_1") (pintype "passive"))
      (node (ref "L1") (pin "1") (pinfunction "1_1") (pintype "passive"))
    )
    (net (code "7") (name "/+5V{slash}3V3_16U2") (class "Default")
      (node (ref "C3") (pin "2") (pinfunction "2_2") (pintype "passive"))
      (node (ref "C4") (pin "2") (pinfunction "2_2") (pintype "passive"))
      (node (ref "C5") (pin "2") (pinfunction "2_2") (pintype "passive"))
      (node (ref "FB1") (pin "2") (pinfunction "2_2") (pintype "passive"))
      (node (ref "R26") (pin "2") (pinfunction "2_2") (pintype "passive"))
      (node (ref "U1") (pin "32") (pinfunction "AVCC_32") (pintype "passive"))
      (node (ref "U1") (pin "4") (pinfunction "VCC_4") (pintype "passive"))
    )
    (net (code "8") (name "/+5V{slash}3V3_328P_AVCC") (class "Default")
      (node (ref "C22") (pin "2") (pinfunction "2_2") (pintype "passive"))
      (node (ref "C23") (pin "2") (pinfunction "2_2") (pintype "passive"))
      (node (ref "FB3") (pin "2") (pinfunction "2_2") (pintype "passive"))
      (node (ref "U3") (pin "20") (pinfunction "AVCC_20") (pintype "passive"))
    )
    (net (code "9") (name "/+5V{slash}3V3_328P_VCC") (class "Default")
      (node (ref "C19") (pin "2") (pinfunction "2_2") (pintype "passive"))
      (node (ref "C20") (pin "2") (pinfunction "2_2") (pintype "passive"))
      (node (ref "FB2") (pin "2") (pinfunction "2_2") (pintype "passive"))
      (node (ref "U3") (pin "7") (pinfunction "VCC_7") (pintype "passive"))
    )
    (net (code "10") (name "/16U2PROG_328P_RESETn") (class "Default")
      (node (ref "JP1") (pin "2") (pinfunction "2_2") (pintype "passive"))
      (node (ref "R1") (pin "1") (pinfunction "1_1") (pintype "passive"))
      (node (ref "U1") (pin "13") (pinfunction "(~{CTS}/~{HWB}/AIN6/TO/INT7)PD7_13") (pintype "passive"))
    )
    (net (code "11") (name "/16U2_16MHZ_XTAL1") (class "Default")
      (node (ref "C10") (pin "2") (pinfunction "2_2") (pintype "passive"))
      (node (ref "R9") (pin "1") (pinfunction "1_1") (pintype "passive"))
      (node (ref "U1") (pin "1") (pinfunction "XTAL1_1") (pintype "passive"))
      (node (ref "Y2") (pin "1") (pinfunction "1_1") (pintype "passive"))
    )
    (net (code "12") (name "/16U2_16MHZ_XTAL2") (class "Default")
      (node (ref "C9") (pin "2") (pinfunction "2_2") (pintype "passive"))
      (node (ref "R9") (pin "2") (pinfunction "2_2") (pintype "passive"))
      (node (ref "U1") (pin "2") (pinfunction "XTAL2(PC0)_2") (pintype "passive"))
      (node (ref "Y2") (pin "2") (pinfunction "2_2") (pintype "passive"))
    )
    (net (code "13") (name "/16U2_MISO") (class "Default")
      (node (ref "J6") (pin "1") (pinfunction "1_1") (pintype "passive"))
      (node (ref "U1") (pin "17") (pinfunction "(PD0/MISO/PCINT3)PB3_17") (pintype "passive"))
    )
    (net (code "14") (name "/16U2_MOSI") (class "Default")
      (node (ref "J6") (pin "4") (pinfunction "4_4") (pintype "passive"))
      (node (ref "U1") (pin "16") (pinfunction "(PDI/MOSI/PCINT2)PB2_16") (pintype "passive"))
    )
    (net (code "15") (name "/16U2_PB4") (class "Default")
      (node (ref "JP2") (pin "1") (pinfunction "1_1") (pintype "passive"))
      (node (ref "JP3") (pin "2") (pinfunction "2_2") (pintype "passive"))
      (node (ref "U1") (pin "18") (pinfunction "(T1/PCINT4)PB4_18") (pintype "passive"))
    )
    (net (code "16") (name "/16U2_PB5") (class "Default")
      (node (ref "JP2") (pin "3") (pinfunction "3_3") (pintype "passive"))
      (node (ref "U1") (pin "19") (pinfunction "(PCINT5)PB5_19") (pintype "passive"))
    )
    (net (code "17") (name "/16U2_PB6") (class "Default")
      (node (ref "JP2") (pin "2") (pinfunction "2_2") (pintype "passive"))
      (node (ref "U1") (pin "20") (pinfunction "(PCINT6)PB6_20") (pintype "passive"))
    )
    (net (code "18") (name "/16U2_PB7") (class "Default")
      (node (ref "JP2") (pin "4") (pinfunction "4_4") (pintype "passive"))
      (node (ref "U1") (pin "21") (pinfunction "(PCINT7/OC0A/OC1C)PB7_21") (pintype "passive"))
    )
    (net (code "19") (name "/16U2_RESETn") (class "Default")
      (node (ref "JP3") (pin "4") (pinfunction "4_4") (pintype "passive"))
      (node (ref "R4") (pin "1") (pinfunction "1_1") (pintype "passive"))
      (node (ref "U1") (pin "24") (pinfunction "PC1/~{RESET}/DW_24") (pintype "passive"))
      (node (ref "U5") (pin "4") (pinfunction "4_4") (pintype "passive"))
    )
    (net (code "20") (name "/16U2_RXT") (class "Default")
      (node (ref "R11") (pin "1") (pinfunction "1_1") (pintype "passive"))
      (node (ref "U1") (pin "8") (pinfunction "(RXD1/AIN1/INT2)PD2_8") (pintype "passive"))
    )
    (net (code "21") (name "/16U2_RX_LED") (class "Default")
      (node (ref "D4") (pin "1") (pinfunction "Cathode_1") (pintype "passive"))
      (node (ref "U1") (pin "10") (pinfunction "(INT5/AIN3)PD4_10") (pintype "passive"))
    )
    (net (code "22") (name "/16U2_TXD") (class "Default")
      (node (ref "R10") (pin "1") (pinfunction "1_1") (pintype "passive"))
      (node (ref "U1") (pin "9") (pinfunction "(TXD1/INT3)PD3_9") (pintype "passive"))
    )
    (net (code "23") (name "/16U2_TX_LED") (class "Default")
      (node (ref "D3") (pin "1") (pinfunction "Cathode_1") (pintype "passive"))
      (node (ref "U1") (pin "11") (pinfunction "(XCK/AIN4/PCINT12)PD5_11") (pintype "passive"))
    )
    (net (code "24") (name "/16U_BUF_RESETn") (class "Default")
      (node (ref "C31") (pin "2") (pinfunction "2_2") (pintype "passive"))
      (node (ref "R23") (pin "2") (pinfunction "2_2") (pintype "passive"))
      (node (ref "U5") (pin "1") (pinfunction "1_1") (pintype "passive"))
      (node (ref "U5") (pin "2") (pinfunction "2_2") (pintype "passive"))
    )
    (net (code "25") (name "/16U_HDR_RESETn") (class "Default")
      (node (ref "J6") (pin "5") (pinfunction "5_5") (pintype "passive"))
      (node (ref "JP3") (pin "3") (pinfunction "3_3") (pintype "passive"))
    )
    (net (code "26") (name "/16U_SCLK") (class "Default")
      (node (ref "J6") (pin "3") (pinfunction "3_3") (pintype "passive"))
      (node (ref "R5") (pin "2") (pinfunction "2_2") (pintype "passive"))
    )
    (net (code "27") (name "/16U_SCLK_R") (class "Default")
      (node (ref "R5") (pin "1") (pinfunction "1_1") (pintype "passive"))
      (node (ref "U1") (pin "15") (pinfunction "(SCLK/PCINT1)PB1_15") (pintype "passive"))
    )
    (net (code "28") (name "/328P_16MHZ_XTAL1") (class "Default")
      (node (ref "C27") (pin "2") (pinfunction "2_2") (pintype "passive"))
      (node (ref "R16") (pin "1") (pinfunction "1_1") (pintype "passive"))
      (node (ref "U3") (pin "9") (pinfunction "PB6_(PCINT6/XTAL1/TOSC1)_9") (pintype "passive"))
      (node (ref "Y1") (pin "1") (pinfunction "1_1") (pintype "passive"))
    )
    (net (code "29") (name "/328P_16MHZ_XTAL2") (class "Default")
      (node (ref "C25") (pin "2") (pinfunction "2_2") (pintype "passive"))
      (node (ref "R16") (pin "2") (pinfunction "2_2") (pintype "passive"))
      (node (ref "U3") (pin "10") (pinfunction "PB7_(PCINT7/XTAL2/TOSC2)_10") (pintype "passive"))
      (node (ref "Y1") (pin "2") (pinfunction "2_2") (pintype "passive"))
    )
    (net (code "30") (name "/328P_AUTORESETn") (class "Default")
      (node (ref "C11") (pin "1") (pinfunction "1_1") (pintype "passive"))
      (node (ref "R18") (pin "1") (pinfunction "1_1") (pintype "passive"))
      (node (ref "U6") (pin "1") (pinfunction "1_1") (pintype "passive"))
    )
    (net (code "31") (name "/328P_BUF_RESETn") (class "Default")
      (node (ref "C32") (pin "2") (pinfunction "2_2") (pintype "passive"))
      (node (ref "R24") (pin "2") (pinfunction "2_2") (pintype "passive"))
      (node (ref "U6") (pin "2") (pinfunction "2_2") (pintype "passive"))
    )
    (net (code "32") (name "/328P_RESETn") (class "Default")
      (node (ref "J1") (pin "3") (pinfunction "3_3") (pintype "passive"))
      (node (ref "J5") (pin "5") (pinfunction "5_5") (pintype "passive"))
      (node (ref "JP3") (pin "1") (pinfunction "1_1") (pintype "passive"))
      (node (ref "R14") (pin "1") (pinfunction "1_1") (pintype "passive"))
      (node (ref "U3") (pin "1") (pinfunction "PC6_(PCINT14/~{RESET})_1") (pintype "passive"))
      (node (ref "U6") (pin "4") (pinfunction "4_4") (pintype "passive"))
    )
    (net (code "33") (name "/AD0") (class "Default")
      (node (ref "J2") (pin "1") (pinfunction "1_1") (pintype "passive"))
      (node (ref "U3") (pin "23") (pinfunction "(ADC0/PCINT8)_PC0_23") (pintype "passive"))
    )
    (net (code "34") (name "/AD1") (class "Default")
      (node (ref "J2") (pin "2") (pinfunction "2_2") (pintype "passive"))
      (node (ref "U3") (pin "24") (pinfunction "(ADC1/PCINT9)_PC1_24") (pintype "passive"))
    )
    (net (code "35") (name "/AD2") (class "Default")
      (node (ref "J2") (pin "3") (pinfunction "3_3") (pintype "passive"))
      (node (ref "U3") (pin "25") (pinfunction "(ADC2/PCINT10)_PC2_25") (pintype "passive"))
    )
    (net (code "36") (name "/AD3") (class "Default")
      (node (ref "J2") (pin "4") (pinfunction "4_4") (pintype "passive"))
      (node (ref "U3") (pin "26") (pinfunction "(ADC3/PCINT11)_PC3_26") (pintype "passive"))
    )
    (net (code "37") (name "/AD4{slash}SDA") (class "Default")
      (node (ref "J2") (pin "5") (pinfunction "5_5") (pintype "passive"))
      (node (ref "J4") (pin "9") (pinfunction "9_9") (pintype "passive"))
      (node (ref "U3") (pin "27") (pinfunction "(ADC4/SDA/PCINT12)_PC4_27") (pintype "passive"))
    )
    (net (code "38") (name "/AD5{slash}SCL") (class "Default")
      (node (ref "J2") (pin "6") (pinfunction "6_6") (pintype "passive"))
      (node (ref "J4") (pin "10") (pinfunction "10_10") (pintype "passive"))
      (node (ref "U3") (pin "28") (pinfunction "(ADC5/SCL/PCINT13)_PC5_28") (pintype "passive"))
    )
    (net (code "39") (name "/BUTTON_RESETn") (class "Default")
      (node (ref "D6") (pin "2") (pinfunction "Anode_2") (pintype "passive"))
      (node (ref "R20") (pin "1") (pinfunction "1_1") (pintype "passive"))
      (node (ref "R24") (pin "1") (pinfunction "1_1") (pintype "passive"))
      (node (ref "SW1") (pin "1") (pinfunction "1_1") (pintype "passive"))
      (node (ref "SW1") (pin "2") (pinfunction "2_2") (pintype "passive"))
    )
    (net (code "40") (name "/CON_USB_N") (class "Default")
      (node (ref "J7") (pin "2") (pinfunction "2_2") (pintype "passive"))
      (node (ref "R6") (pin "1") (pinfunction "1_1") (pintype "passive"))
      (node (ref "Z1") (pin "2") (pinfunction "2_2") (pintype "passive"))
    )
    (net (code "41") (name "/CON_USB_P") (class "Default")
      (node (ref "J7") (pin "3") (pinfunction "3_3") (pintype "passive"))
      (node (ref "R7") (pin "1") (pinfunction "1_1") (pintype "passive"))
      (node (ref "Z2") (pin "2") (pinfunction "2_2") (pintype "passive"))
    )
    (net (code "42") (name "/IO0") (class "Default")
      (node (ref "J3") (pin "1") (pinfunction "1_1") (pintype "passive"))
      (node (ref "R10") (pin "2") (pinfunction "2_2") (pintype "passive"))
      (node (ref "U3") (pin "2") (pinfunction "(PCINT16/RXD)_PD0_2") (pintype "passive"))
    )
    (net (code "43") (name "/IO1") (class "Default")
      (node (ref "J3") (pin "2") (pinfunction "2_2") (pintype "passive"))
      (node (ref "R11") (pin "2") (pinfunction "2_2") (pintype "passive"))
      (node (ref "U3") (pin "3") (pinfunction "(PCINT17/TXD)_PD1_3") (pintype "passive"))
    )
    (net (code "44") (name "/IO2") (class "Default")
      (node (ref "J3") (pin "3") (pinfunction "3_3") (pintype "passive"))
      (node (ref "U3") (pin "4") (pinfunction "(PCINT18/INT0)_PD2_4") (pintype "passive"))
    )
    (net (code "45") (name "/IO3") (class "Default")
      (node (ref "J3") (pin "4") (pinfunction "4_4") (pintype "passive"))
      (node (ref "U3") (pin "5") (pinfunction "(PCINT19/OC2B/INT1)_PD3_5") (pintype "passive"))
    )
    (net (code "46") (name "/IO4") (class "Default")
      (node (ref "J3") (pin "5") (pinfunction "5_5") (pintype "passive"))
      (node (ref "U3") (pin "6") (pinfunction "(PCINT20/XCK/T0)_PD4_6") (pintype "passive"))
    )
    (net (code "47") (name "/IO5") (class "Default")
      (node (ref "J3") (pin "6") (pinfunction "6_6") (pintype "passive"))
      (node (ref "U3") (pin "11") (pinfunction "(PCINT21/OC0B/T1)_PD5_11") (pintype "passive"))
    )
    (net (code "48") (name "/IO6") (class "Default")
      (node (ref "J3") (pin "7") (pinfunction "7_7") (pintype "passive"))
      (node (ref "U3") (pin "12") (pinfunction "(PCINT22/OC0A/AIN0)_PD6_12") (pintype "passive"))
    )
    (net (code "49") (name "/IO7") (class "Default")
      (node (ref "J3") (pin "8") (pinfunction "8_8") (pintype "passive"))
      (node (ref "U3") (pin "13") (pinfunction "(PCINT23/AIN1)_PD7_13") (pintype "passive"))
    )
    (net (code "50") (name "/IO8") (class "Default")
      (node (ref "J4") (pin "1") (pinfunction "1_1") (pintype "passive"))
      (node (ref "R22") (pin "2") (pinfunction "2_2") (pintype "passive"))
      (node (ref "U3") (pin "14") (pinfunction "(PCINT0/CLKO/ICP1)_PB0_14") (pintype "passive"))
    )
    (net (code "51") (name "/IO9") (class "Default")
      (node (ref "J4") (pin "2") (pinfunction "2_2") (pintype "passive"))
      (node (ref "U3") (pin "15") (pinfunction "(OC1A/PCINT1)_PB1_15") (pintype "passive"))
    )
    (net (code "52") (name "/MISO") (class "Default")
      (node (ref "J4") (pin "5") (pinfunction "5_5") (pintype "passive"))
      (node (ref "J5") (pin "1") (pinfunction "1_1") (pintype "passive"))
      (node (ref "U3") (pin "18") (pinfunction "(MISO/PCINT4)_PB4_18") (pintype "passive"))
    )
    (net (code "53") (name "/MOSI") (class "Default")
      (node (ref "J4") (pin "4") (pinfunction "4_4") (pintype "passive"))
      (node (ref "J5") (pin "4") (pinfunction "4_4") (pintype "passive"))
      (node (ref "U3") (pin "17") (pinfunction "(MOSI/OC2A/PCINT3)_PB3_17") (pintype "passive"))
    )
    (net (code "54") (name "/SCK") (class "Default")
      (node (ref "J4") (pin "6") (pinfunction "6_6") (pintype "passive"))
      (node (ref "J5") (pin "3") (pinfunction "3_3") (pintype "passive"))
      (node (ref "R13") (pin "2") (pinfunction "2_2") (pintype "passive"))
      (node (ref "U4") (pin "1") (pinfunction "1_1") (pintype "passive"))
      (node (ref "U4") (pin "2") (pinfunction "2_2") (pintype "passive"))
    )
    (net (code "55") (name "/SCK_R") (class "Default")
      (node (ref "R13") (pin "1") (pinfunction "1_1") (pintype "passive"))
      (node (ref "U3") (pin "19") (pinfunction "_(SCK/PCINT5)_PB5_19") (pintype "passive"))
    )
    (net (code "56") (name "/SS") (class "Default")
      (node (ref "J4") (pin "3") (pinfunction "3_3") (pintype "passive"))
      (node (ref "U3") (pin "16") (pinfunction "(~{SS}/OC1B/PCINT2)_PB2_16") (pintype "passive"))
    )
    (net (code "57") (name "/USB_N") (class "Default")
      (node (ref "R6") (pin "2") (pinfunction "2_2") (pintype "passive"))
      (node (ref "U1") (pin "30") (pinfunction "D-_30") (pintype "passive"))
    )
    (net (code "58") (name "/USB_P") (class "Default")
      (node (ref "R7") (pin "2") (pinfunction "2_2") (pintype "passive"))
      (node (ref "U1") (pin "29") (pinfunction "D+_29") (pintype "passive"))
    )
    (net (code "59") (name "/USER_BUTTON") (class "Default")
      (node (ref "R21") (pin "1") (pinfunction "1_1") (pintype "passive"))
      (node (ref "R25") (pin "1") (pinfunction "1_1") (pintype "passive"))
      (node (ref "SW2") (pin "1") (pinfunction "1_1") (pintype "passive"))
      (node (ref "SW2") (pin "2") (pinfunction "2_2") (pintype "passive"))
    )
    (net (code "60") (name "/USER_BUTTON_BUF") (class "Default")
      (node (ref "C33") (pin "2") (pinfunction "2_2") (pintype "passive"))
      (node (ref "R25") (pin "2") (pinfunction "2_2") (pintype "passive"))
      (node (ref "U7") (pin "1") (pinfunction "1_1") (pintype "passive"))
      (node (ref "U7") (pin "2") (pinfunction "2_2") (pintype "passive"))
    )
    (net (code "61") (name "GND") (class "Default")
      (node (ref "C1") (pin "2") (pinfunction "2_2") (pintype "passive"))
      (node (ref "C10") (pin "1") (pinfunction "1_1") (pintype "passive"))
      (node (ref "C12") (pin "1") (pinfunction "1_1") (pintype "passive"))
      (node (ref "C13") (pin "1") (pinfunction "1_1") (pintype "passive"))
      (node (ref "C14") (pin "1") (pinfunction "1_1") (pintype "passive"))
      (node (ref "C15") (pin "1") (pinfunction "1_1") (pintype "passive"))
      (node (ref "C16") (pin "1") (pinfunction "1_1") (pintype "passive"))
      (node (ref "C17") (pin "1") (pinfunction "1_1") (pintype "passive"))
      (node (ref "C19") (pin "1") (pinfunction "1_1") (pintype "passive"))
      (node (ref "C2") (pin "2") (pinfunction "2_2") (pintype "passive"))
      (node (ref "C20") (pin "1") (pinfunction "1_1") (pintype "passive"))
      (node (ref "C21") (pin "1") (pinfunction "1_1") (pintype "passive"))
      (node (ref "C22") (pin "1") (pinfunction "1_1") (pintype "passive"))
      (node (ref "C23") (pin "1") (pinfunction "1_1") (pintype "passive"))
      (node (ref "C24") (pin "2") (pinfunction "2_2") (pintype "passive"))
      (node (ref "C25") (pin "1") (pinfunction "1_1") (pintype "passive"))
      (node (ref "C26") (pin "1") (pinfunction "1_1") (pintype "passive"))
      (node (ref "C27") (pin "1") (pinfunction "1_1") (pintype "passive"))
      (node (ref "C28") (pin "1") (pinfunction "1_1") (pintype "passive"))
      (node (ref "C29") (pin "1") (pinfunction "1_1") (pintype "passive"))
      (node (ref "C3") (pin "1") (pinfunction "1_1") (pintype "passive"))
      (node (ref "C30") (pin "1") (pinfunction "1_1") (pintype "passive"))
      (node (ref "C31") (pin "1") (pinfunction "1_1") (pintype "passive"))
      (node (ref "C32") (pin "1") (pinfunction "1_1") (pintype "passive"))
      (node (ref "C33") (pin "1") (pinfunction "1_1") (pintype "passive"))
      (node (ref "C34") (pin "1") (pinfunction "1_1") (pintype "passive"))
      (node (ref "C4") (pin "1") (pinfunction "1_1") (pintype "passive"))
      (node (ref "C5") (pin "1") (pinfunction "1_1") (pintype "passive"))
      (node (ref "C6") (pin "1") (pinfunction "1_1") (pintype "passive"))
      (node (ref "C7") (pin "1") (pinfunction "1_1") (pintype "passive"))
      (node (ref "C8") (pin "1") (pinfunction "1_1") (pintype "passive"))
      (node (ref "C9") (pin "1") (pinfunction "1_1") (pintype "passive"))
      (node (ref "D1") (pin "1") (pinfunction "Cathode_1") (pintype "passive"))
      (node (ref "J1") (pin "6") (pinfunction "6_6") (pintype "passive"))
      (node (ref "J1") (pin "7") (pinfunction "7_7") (pintype "passive"))
      (node (ref "J4") (pin "7") (pinfunction "7_7") (pintype "passive"))
      (node (ref "J5") (pin "6") (pinfunction "6_6") (pintype "passive"))
      (node (ref "J6") (pin "6") (pinfunction "6_6") (pintype "passive"))
      (node (ref "J7") (pin "10") (pinfunction "10_10") (pintype "passive"))
      (node (ref "J7") (pin "11") (pinfunction "11_11") (pintype "passive"))
      (node (ref "J7") (pin "5") (pinfunction "5_5") (pintype "passive"))
      (node (ref "J7") (pin "6") (pinfunction "6_6") (pintype "passive"))
      (node (ref "J7") (pin "7") (pinfunction "7_7") (pintype "passive"))
      (node (ref "J7") (pin "8") (pinfunction "8_8") (pintype "passive"))
      (node (ref "J7") (pin "9") (pinfunction "9_9") (pintype "passive"))
      (node (ref "R12") (pin "1") (pinfunction "1_1") (pintype "passive"))
      (node (ref "R8") (pin "2") (pinfunction "2_2") (pintype "passive"))
      (node (ref "SW1") (pin "3") (pinfunction "3_3") (pintype "passive"))
      (node (ref "SW1") (pin "4") (pinfunction "4_4") (pintype "passive"))
      (node (ref "SW2") (pin "3") (pinfunction "3_3") (pintype "passive"))
      (node (ref "SW2") (pin "4") (pinfunction "4_4") (pintype "passive"))
      (node (ref "U1") (pin "28") (pinfunction "UGND_28") (pintype "passive"))
      (node (ref "U1") (pin "3") (pinfunction "GND_3") (pintype "passive"))
      (node (ref "U2") (pin "3") (pinfunction "GND_3") (pintype "passive"))
      (node (ref "U2") (pin "6") (pinfunction "EPAD_6") (pintype "passive"))
      (node (ref "U3") (pin "22") (pinfunction "GND_2_22") (pintype "passive"))
      (node (ref "U3") (pin "8") (pinfunction "GND_1_8") (pintype "passive"))
      (node (ref "U4") (pin "3") (pinfunction "3_3") (pintype "passive"))
      (node (ref "U5") (pin "3") (pinfunction "3_3") (pintype "passive"))
      (node (ref "U6") (pin "3") (pinfunction "3_3") (pintype "passive"))
      (node (ref "U7") (pin "3") (pinfunction "3_3") (pintype "passive"))
      (node (ref "Z1") (pin "1") (pinfunction "1_1") (pintype "passive"))
      (node (ref "Z2") (pin "1") (pinfunction "1_1") (pintype "passive"))
    )
    (net (code "62") (name "Net-(C11-Pad2)") (class "Default")
      (node (ref "C11") (pin "2") (pinfunction "2_2") (pintype "passive"))
      (node (ref "JP1") (pin "1") (pinfunction "1_1") (pintype "passive"))
    )
    (net (code "63") (name "Net-(D1-Anode)") (class "Default")
      (node (ref "D1") (pin "2") (pinfunction "Anode_2") (pintype "passive"))
      (node (ref "R17") (pin "1") (pinfunction "1_1") (pintype "passive"))
    )
    (net (code "64") (name "Net-(D2-Anode)") (class "Default")
      (node (ref "D2") (pin "2") (pinfunction "Anode_2") (pintype "passive"))
      (node (ref "R15") (pin "1") (pinfunction "1_1") (pintype "passive"))
    )
    (net (code "65") (name "Net-(D2-Cathode)") (class "Default")
      (node (ref "D2") (pin "1") (pinfunction "Cathode_1") (pintype "passive"))
      (node (ref "U4") (pin "4") (pinfunction "4_4") (pintype "passive"))
    )
    (net (code "66") (name "Net-(D3-Anode)") (class "Default")
      (node (ref "D3") (pin "2") (pinfunction "Anode_2") (pintype "passive"))
      (node (ref "R2") (pin "1") (pinfunction "1_1") (pintype "passive"))
    )
    (net (code "67") (name "Net-(D4-Anode)") (class "Default")
      (node (ref "D4") (pin "2") (pinfunction "Anode_2") (pintype "passive"))
      (node (ref "R3") (pin "1") (pinfunction "1_1") (pintype "passive"))
    )
    (net (code "68") (name "Net-(D5-Anode)") (class "Default")
      (node (ref "D5") (pin "2") (pinfunction "Anode_2") (pintype "passive"))
      (node (ref "R19") (pin "1") (pinfunction "1_1") (pintype "passive"))
      (node (ref "R23") (pin "1") (pinfunction "1_1") (pintype "passive"))
    )
    (net (code "69") (name "Net-(J7-Pad4)") (class "Default")
      (node (ref "J7") (pin "4") (pinfunction "4_4") (pintype "passive"))
      (node (ref "R8") (pin "1") (pinfunction "1_1") (pintype "passive"))
    )
    (net (code "70") (name "Net-(JP1-Pad3)") (class "Default")
      (node (ref "JP1") (pin "3") (pinfunction "3_3") (pintype "passive"))
      (node (ref "R12") (pin "2") (pinfunction "2_2") (pintype "passive"))
    )
    (net (code "71") (name "Net-(R22-Pad1)") (class "Default")
      (node (ref "R22") (pin "1") (pinfunction "1_1") (pintype "passive"))
      (node (ref "U7") (pin "4") (pinfunction "4_4") (pintype "passive"))
    )
    (net (code "72") (name "unconnected-(J1-Pad1)") (class "Default")
      (node (ref "J1") (pin "1") (pinfunction "1_1") (pintype "passive+no_connect"))
    )
    (net (code "73") (name "unconnected-(J1-Pad8)") (class "Default")
      (node (ref "J1") (pin "8") (pinfunction "8_8") (pintype "passive+no_connect"))
    )
    (net (code "74") (name "unconnected-(U1-(AIN0{slash}INT1)PD1-Pad7)") (class "Default")
      (node (ref "U1") (pin "7") (pinfunction "(AIN0/INT1)PD1_7") (pintype "passive+no_connect"))
    )
    (net (code "75") (name "unconnected-(U1-(AIN2{slash}PCINT11)PC2-Pad5)") (class "Default")
      (node (ref "U1") (pin "5") (pinfunction "(AIN2/PCINT11)PC2_5") (pintype "passive+no_connect"))
    )
    (net (code "76") (name "unconnected-(U1-(INT4{slash}ICP1{slash}CLK0)PC7-Pad22)") (class "Default")
      (node (ref "U1") (pin "22") (pinfunction "(INT4/ICP1/CLK0)PC7_22") (pintype "passive+no_connect"))
    )
    (net (code "77") (name "unconnected-(U1-(OC0B{slash}INT0)PD0-Pad6)") (class "Default")
      (node (ref "U1") (pin "6") (pinfunction "(OC0B/INT0)PD0_6") (pintype "passive+no_connect"))
    )
    (net (code "78") (name "unconnected-(U1-(OC1A{slash}PCINT8)PC6-Pad23)") (class "Default")
      (node (ref "U1") (pin "23") (pinfunction "(OC1A/PCINT8)PC6_23") (pintype "passive+no_connect"))
    )
    (net (code "79") (name "unconnected-(U1-(PCINT9{slash}OC1B)PC5-Pad25)") (class "Default")
      (node (ref "U1") (pin "25") (pinfunction "(PCINT9/OC1B)PC5_25") (pintype "passive+no_connect"))
    )
    (net (code "80") (name "unconnected-(U1-(PCINT10)PC4-Pad26)") (class "Default")
      (node (ref "U1") (pin "26") (pinfunction "(PCINT10)PC4_26") (pintype "passive+no_connect"))
    )
    (net (code "81") (name "unconnected-(U1-(SS{slash}PCINT0)PB0-Pad14)") (class "Default")
      (node (ref "U1") (pin "14") (pinfunction "(SS/PCINT0)PB0_14") (pintype "passive+no_connect"))
    )
    (net (code "82") (name "unconnected-(U1-(~{RTS}{slash}AIN5{slash}INT6)PD6-Pad12)") (class "Default")
      (node (ref "U1") (pin "12") (pinfunction "(~{RTS}/AIN5/INT6)PD6_12") (pintype "passive+no_connect"))
    )
  )
)
